# my_tic_tac_toe_board.net
KiCad netlist of a schematic drawn in EAGLE
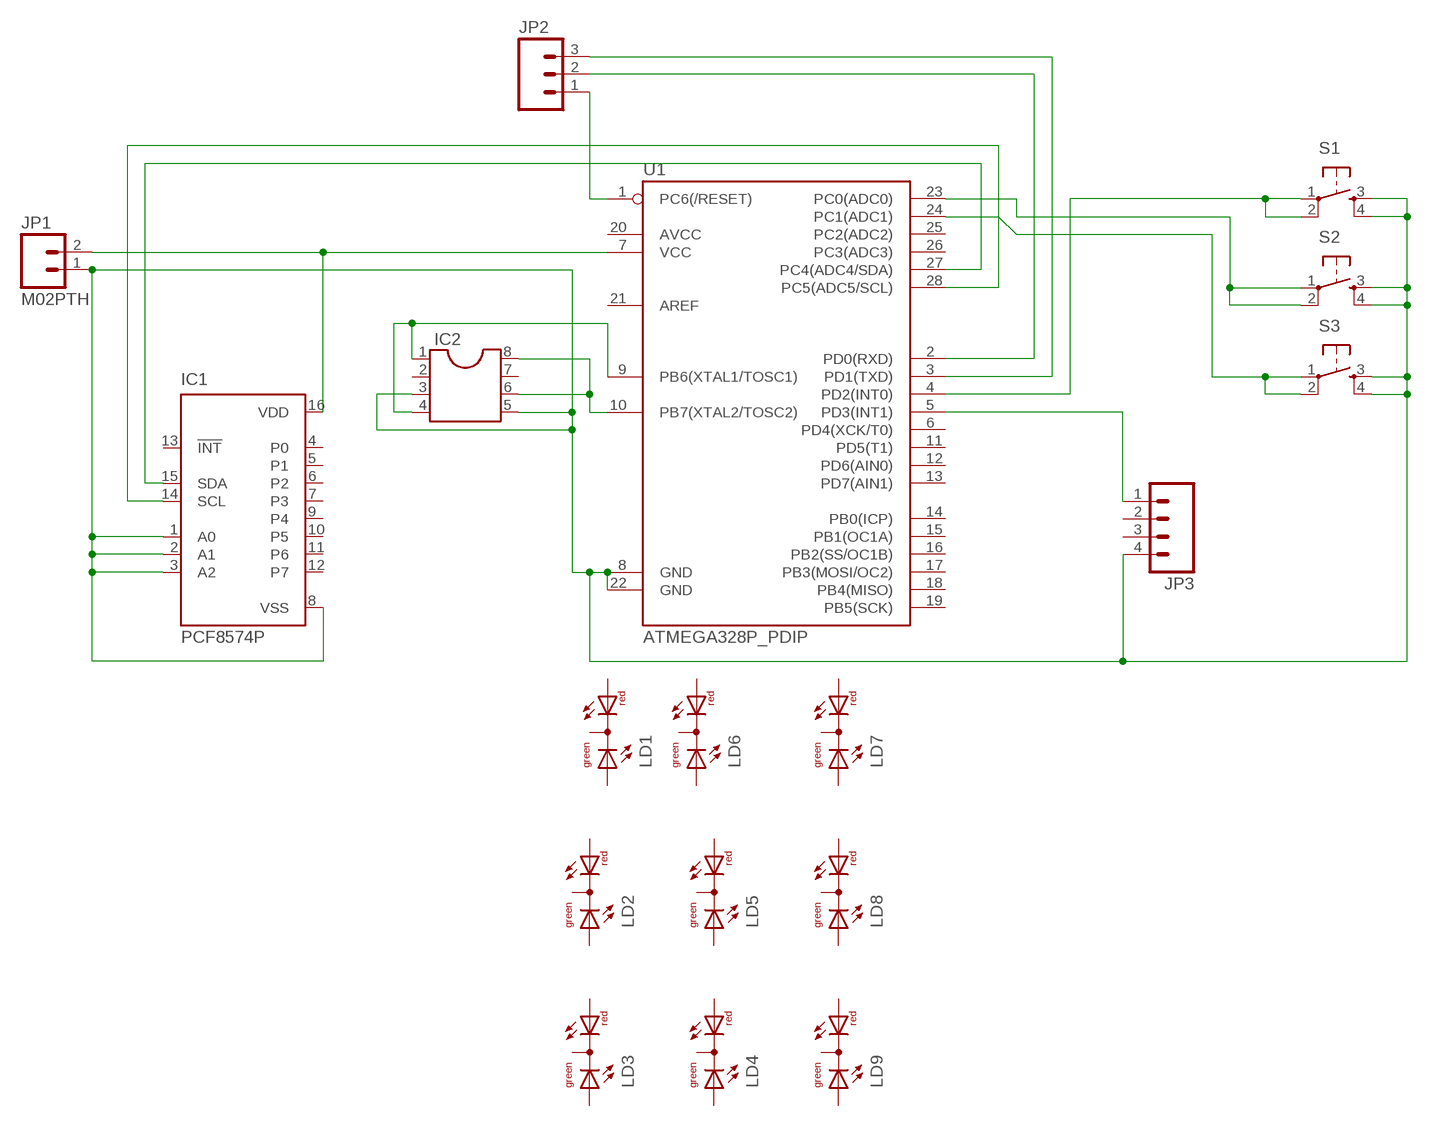
[diagram p0: schematic, sheet 1]

(export (version "E")
  (design (tool "Eeschema 10.0.6"))
  (components
    (comp (ref "IC1")
      (value "PCF8574P")
      (footprint "eagle-import:DIL16")
      (fields (field (name "MPN") "PCF8574PN"))
      (libsource (lib "eagle-import") (part "PCF8574P"))
    )
    (comp (ref "IC2")
      (value "DIL8S")
      (footprint "eagle-import:SOCKET-08")
      (libsource (lib "eagle-import") (part "DIL8S"))
    )
    (comp (ref "JP1")
      (value "M02PTH")
      (footprint "eagle-import:1X02")
      (libsource (lib "eagle-import") (part "M02PTH"))
    )
    (comp (ref "JP2")
      (value "M03PTH")
      (footprint "eagle-import:1X03")
      (libsource (lib "eagle-import") (part "M03PTH"))
    )
    (comp (ref "JP3")
      (value "M04PTH")
      (footprint "eagle-import:1X04")
      (libsource (lib "eagle-import") (part "M04PTH"))
    )
    (comp (ref "LD1")
      (value "DUOLED-RG-C")
      (footprint "eagle-import:DUOLED-C-5MM")
      (libsource (lib "eagle-import") (part "DUOLED-RG-C"))
    )
    (comp (ref "LD2")
      (value "DUOLED-RG-C")
      (footprint "eagle-import:DUOLED-C-5MM")
      (libsource (lib "eagle-import") (part "DUOLED-RG-C"))
    )
    (comp (ref "LD3")
      (value "DUOLED-RG-C")
      (footprint "eagle-import:DUOLED-C-5MM")
      (libsource (lib "eagle-import") (part "DUOLED-RG-C"))
    )
    (comp (ref "LD4")
      (value "DUOLED-RG-C")
      (footprint "eagle-import:DUOLED-C-5MM")
      (libsource (lib "eagle-import") (part "DUOLED-RG-C"))
    )
    (comp (ref "LD5")
      (value "DUOLED-RG-C")
      (footprint "eagle-import:DUOLED-C-5MM")
      (libsource (lib "eagle-import") (part "DUOLED-RG-C"))
    )
    (comp (ref "LD6")
      (value "DUOLED-RG-C")
      (footprint "eagle-import:DUOLED-C-5MM")
      (libsource (lib "eagle-import") (part "DUOLED-RG-C"))
    )
    (comp (ref "LD7")
      (value "DUOLED-RG-C")
      (footprint "eagle-import:DUOLED-C-5MM")
      (libsource (lib "eagle-import") (part "DUOLED-RG-C"))
    )
    (comp (ref "LD8")
      (value "DUOLED-RG-C")
      (footprint "eagle-import:DUOLED-C-5MM")
      (libsource (lib "eagle-import") (part "DUOLED-RG-C"))
    )
    (comp (ref "LD9")
      (value "DUOLED-RG-C")
      (footprint "eagle-import:DUOLED-C-5MM")
      (libsource (lib "eagle-import") (part "DUOLED-RG-C"))
    )
    (comp (ref "S1")
      (value "TAC_SWITCHPTH")
      (footprint "eagle-import:TACTILE-PTH")
      (libsource (lib "eagle-import") (part "TAC_SWITCHPTH"))
    )
    (comp (ref "S2")
      (value "TAC_SWITCHPTH")
      (footprint "eagle-import:TACTILE-PTH")
      (libsource (lib "eagle-import") (part "TAC_SWITCHPTH"))
    )
    (comp (ref "S3")
      (value "TAC_SWITCHPTH")
      (footprint "eagle-import:TACTILE-PTH")
      (libsource (lib "eagle-import") (part "TAC_SWITCHPTH"))
    )
    (comp (ref "U1")
      (value "ATMEGA328P_PDIP")
      (footprint "eagle-import:DIL28-3")
      (libsource (lib "eagle-import") (part "ATMEGA328P_PDIP"))
    )
  )
  (nets
    (net (code "1") (name "Net-(IC1-A0)") (class "Default")
      (node (ref "IC1") (pin "1") (pinfunction "A0_1") (pintype "input"))
      (node (ref "IC1") (pin "2") (pinfunction "A1_2") (pintype "input"))
      (node (ref "IC1") (pin "3") (pinfunction "A2_3") (pintype "input"))
      (node (ref "IC1") (pin "8") (pinfunction "VSS_8") (pintype "power_in"))
      (node (ref "IC2") (pin "3") (pinfunction "3_3") (pintype "passive"))
      (node (ref "IC2") (pin "5") (pinfunction "5_5") (pintype "passive"))
      (node (ref "JP1") (pin "1") (pinfunction "1_1") (pintype "passive"))
      (node (ref "JP3") (pin "4") (pinfunction "4_4") (pintype "passive"))
      (node (ref "S1") (pin "3") (pinfunction "3_3") (pintype "passive"))
      (node (ref "S1") (pin "4") (pinfunction "4_4") (pintype "passive"))
      (node (ref "S2") (pin "3") (pinfunction "3_3") (pintype "passive"))
      (node (ref "S2") (pin "4") (pinfunction "4_4") (pintype "passive"))
      (node (ref "S3") (pin "3") (pinfunction "3_3") (pintype "passive"))
      (node (ref "S3") (pin "4") (pinfunction "4_4") (pintype "passive"))
      (node (ref "U1") (pin "22") (pinfunction "GND_22") (pintype "bidirectional"))
      (node (ref "U1") (pin "8") (pinfunction "GND_8") (pintype "bidirectional"))
    )
    (net (code "2") (name "Net-(IC1-SCL)") (class "Default")
      (node (ref "IC1") (pin "14") (pinfunction "SCL_14") (pintype "input"))
      (node (ref "U1") (pin "28") (pinfunction "PC5(ADC5/SCL)_28") (pintype "bidirectional"))
    )
    (net (code "3") (name "Net-(IC1-SDA)") (class "Default")
      (node (ref "IC1") (pin "15") (pinfunction "SDA_15") (pintype "bidirectional"))
      (node (ref "U1") (pin "27") (pinfunction "PC4(ADC4/SDA)_27") (pintype "bidirectional"))
    )
    (net (code "4") (name "Net-(IC1-VDD)") (class "Default")
      (node (ref "IC1") (pin "16") (pinfunction "VDD_16") (pintype "power_in"))
      (node (ref "JP1") (pin "2") (pinfunction "2_2") (pintype "passive"))
      (node (ref "U1") (pin "7") (pinfunction "VCC_7") (pintype "bidirectional"))
    )
    (net (code "5") (name "Net-(U1-PB6(XTAL1{slash}TOSC1))") (class "Default")
      (node (ref "IC2") (pin "1") (pinfunction "1_1") (pintype "passive"))
      (node (ref "IC2") (pin "4") (pinfunction "4_4") (pintype "passive"))
      (node (ref "U1") (pin "9") (pinfunction "PB6(XTAL1/TOSC1)_9") (pintype "bidirectional"))
    )
    (net (code "6") (name "Net-(U1-PB7(XTAL2{slash}TOSC2))") (class "Default")
      (node (ref "IC2") (pin "6") (pinfunction "6_6") (pintype "passive"))
      (node (ref "IC2") (pin "8") (pinfunction "8_8") (pintype "passive"))
      (node (ref "U1") (pin "10") (pinfunction "PB7(XTAL2/TOSC2)_10") (pintype "bidirectional"))
    )
    (net (code "7") (name "Net-(U1-PC0(ADC0))") (class "Default")
      (node (ref "S2") (pin "1") (pinfunction "1_1") (pintype "passive"))
      (node (ref "S2") (pin "2") (pinfunction "2_2") (pintype "passive"))
      (node (ref "U1") (pin "23") (pinfunction "PC0(ADC0)_23") (pintype "bidirectional"))
    )
    (net (code "8") (name "Net-(U1-PC1(ADC1))") (class "Default")
      (node (ref "S3") (pin "1") (pinfunction "1_1") (pintype "passive"))
      (node (ref "S3") (pin "2") (pinfunction "2_2") (pintype "passive"))
      (node (ref "U1") (pin "24") (pinfunction "PC1(ADC1)_24") (pintype "bidirectional"))
    )
    (net (code "9") (name "Net-(U1-PC6({slash}RESET))") (class "Default")
      (node (ref "JP2") (pin "1") (pinfunction "1_1") (pintype "passive"))
      (node (ref "U1") (pin "1") (pinfunction "PC6(/RESET)_1") (pintype "bidirectional"))
    )
    (net (code "10") (name "Net-(U1-PD0(RXD))") (class "Default")
      (node (ref "JP2") (pin "2") (pinfunction "2_2") (pintype "passive"))
      (node (ref "U1") (pin "2") (pinfunction "PD0(RXD)_2") (pintype "bidirectional"))
    )
    (net (code "11") (name "Net-(U1-PD1(TXD))") (class "Default")
      (node (ref "JP2") (pin "3") (pinfunction "3_3") (pintype "passive"))
      (node (ref "U1") (pin "3") (pinfunction "PD1(TXD)_3") (pintype "bidirectional"))
    )
    (net (code "12") (name "Net-(U1-PD2(INT0))") (class "Default")
      (node (ref "S1") (pin "1") (pinfunction "1_1") (pintype "passive"))
      (node (ref "S1") (pin "2") (pinfunction "2_2") (pintype "passive"))
      (node (ref "U1") (pin "4") (pinfunction "PD2(INT0)_4") (pintype "bidirectional"))
    )
    (net (code "13") (name "Net-(U1-PD3(INT1))") (class "Default")
      (node (ref "JP3") (pin "1") (pinfunction "1_1") (pintype "passive"))
      (node (ref "U1") (pin "5") (pinfunction "PD3(INT1)_5") (pintype "bidirectional"))
    )
    (net (code "14") (name "unconnected-(IC1-P0-Pad4)") (class "Default")
      (node (ref "IC1") (pin "4") (pinfunction "P0_4") (pintype "bidirectional"))
    )
    (net (code "15") (name "unconnected-(IC1-P1-Pad5)") (class "Default")
      (node (ref "IC1") (pin "5") (pinfunction "P1_5") (pintype "bidirectional"))
    )
    (net (code "16") (name "unconnected-(IC1-P2-Pad6)") (class "Default")
      (node (ref "IC1") (pin "6") (pinfunction "P2_6") (pintype "bidirectional"))
    )
    (net (code "17") (name "unconnected-(IC1-P3-Pad7)") (class "Default")
      (node (ref "IC1") (pin "7") (pinfunction "P3_7") (pintype "bidirectional"))
    )
    (net (code "18") (name "unconnected-(IC1-P4-Pad9)") (class "Default")
      (node (ref "IC1") (pin "9") (pinfunction "P4_9") (pintype "bidirectional"))
    )
    (net (code "19") (name "unconnected-(IC1-P5-Pad10)") (class "Default")
      (node (ref "IC1") (pin "10") (pinfunction "P5_10") (pintype "bidirectional"))
    )
    (net (code "20") (name "unconnected-(IC1-P6-Pad11)") (class "Default")
      (node (ref "IC1") (pin "11") (pinfunction "P6_11") (pintype "bidirectional"))
    )
    (net (code "21") (name "unconnected-(IC1-P7-Pad12)") (class "Default")
      (node (ref "IC1") (pin "12") (pinfunction "P7_12") (pintype "bidirectional"))
    )
    (net (code "22") (name "unconnected-(IC1-~{INT}-Pad13)") (class "Default")
      (node (ref "IC1") (pin "13") (pinfunction "~{INT}_13") (pintype "output"))
    )
    (net (code "23") (name "unconnected-(IC2-Pad2)") (class "Default")
      (node (ref "IC2") (pin "2") (pinfunction "2_2") (pintype "passive"))
    )
    (net (code "24") (name "unconnected-(IC2-Pad7)") (class "Default")
      (node (ref "IC2") (pin "7") (pinfunction "7_7") (pintype "passive"))
    )
    (net (code "25") (name "unconnected-(JP3-Pad2)") (class "Default")
      (node (ref "JP3") (pin "2") (pinfunction "2_2") (pintype "passive"))
    )
    (net (code "26") (name "unconnected-(JP3-Pad3)") (class "Default")
      (node (ref "JP3") (pin "3") (pinfunction "3_3") (pintype "passive"))
    )
    (net (code "27") (name "unconnected-(LD1-AG-PadAX)") (class "Default")
      (node (ref "LD1") (pin "AX") (pinfunction "AG_AX") (pintype "passive"))
    )
    (net (code "28") (name "unconnected-(LD1-PadAR)") (class "Default")
      (node (ref "LD1") (pin "AR") (pinfunction "AR_AR") (pintype "passive"))
    )
    (net (code "29") (name "unconnected-(LD1-PadC)") (class "Default")
      (node (ref "LD1") (pin "C") (pinfunction "C_C") (pintype "passive"))
    )
    (net (code "30") (name "unconnected-(LD2-AG-PadAX)") (class "Default")
      (node (ref "LD2") (pin "AX") (pinfunction "AG_AX") (pintype "passive"))
    )
    (net (code "31") (name "unconnected-(LD2-PadAR)") (class "Default")
      (node (ref "LD2") (pin "AR") (pinfunction "AR_AR") (pintype "passive"))
    )
    (net (code "32") (name "unconnected-(LD2-PadC)") (class "Default")
      (node (ref "LD2") (pin "C") (pinfunction "C_C") (pintype "passive"))
    )
    (net (code "33") (name "unconnected-(LD3-AG-PadAX)") (class "Default")
      (node (ref "LD3") (pin "AX") (pinfunction "AG_AX") (pintype "passive"))
    )
    (net (code "34") (name "unconnected-(LD3-PadAR)") (class "Default")
      (node (ref "LD3") (pin "AR") (pinfunction "AR_AR") (pintype "passive"))
    )
    (net (code "35") (name "unconnected-(LD3-PadC)") (class "Default")
      (node (ref "LD3") (pin "C") (pinfunction "C_C") (pintype "passive"))
    )
    (net (code "36") (name "unconnected-(LD4-AG-PadAX)") (class "Default")
      (node (ref "LD4") (pin "AX") (pinfunction "AG_AX") (pintype "passive"))
    )
    (net (code "37") (name "unconnected-(LD4-PadAR)") (class "Default")
      (node (ref "LD4") (pin "AR") (pinfunction "AR_AR") (pintype "passive"))
    )
    (net (code "38") (name "unconnected-(LD4-PadC)") (class "Default")
      (node (ref "LD4") (pin "C") (pinfunction "C_C") (pintype "passive"))
    )
    (net (code "39") (name "unconnected-(LD5-AG-PadAX)") (class "Default")
      (node (ref "LD5") (pin "AX") (pinfunction "AG_AX") (pintype "passive"))
    )
    (net (code "40") (name "unconnected-(LD5-PadAR)") (class "Default")
      (node (ref "LD5") (pin "AR") (pinfunction "AR_AR") (pintype "passive"))
    )
    (net (code "41") (name "unconnected-(LD5-PadC)") (class "Default")
      (node (ref "LD5") (pin "C") (pinfunction "C_C") (pintype "passive"))
    )
    (net (code "42") (name "unconnected-(LD6-AG-PadAX)") (class "Default")
      (node (ref "LD6") (pin "AX") (pinfunction "AG_AX") (pintype "passive"))
    )
    (net (code "43") (name "unconnected-(LD6-PadAR)") (class "Default")
      (node (ref "LD6") (pin "AR") (pinfunction "AR_AR") (pintype "passive"))
    )
    (net (code "44") (name "unconnected-(LD6-PadC)") (class "Default")
      (node (ref "LD6") (pin "C") (pinfunction "C_C") (pintype "passive"))
    )
    (net (code "45") (name "unconnected-(LD7-AG-PadAX)") (class "Default")
      (node (ref "LD7") (pin "AX") (pinfunction "AG_AX") (pintype "passive"))
    )
    (net (code "46") (name "unconnected-(LD7-PadAR)") (class "Default")
      (node (ref "LD7") (pin "AR") (pinfunction "AR_AR") (pintype "passive"))
    )
    (net (code "47") (name "unconnected-(LD7-PadC)") (class "Default")
      (node (ref "LD7") (pin "C") (pinfunction "C_C") (pintype "passive"))
    )
    (net (code "48") (name "unconnected-(LD8-AG-PadAX)") (class "Default")
      (node (ref "LD8") (pin "AX") (pinfunction "AG_AX") (pintype "passive"))
    )
    (net (code "49") (name "unconnected-(LD8-PadAR)") (class "Default")
      (node (ref "LD8") (pin "AR") (pinfunction "AR_AR") (pintype "passive"))
    )
    (net (code "50") (name "unconnected-(LD8-PadC)") (class "Default")
      (node (ref "LD8") (pin "C") (pinfunction "C_C") (pintype "passive"))
    )
    (net (code "51") (name "unconnected-(LD9-AG-PadAX)") (class "Default")
      (node (ref "LD9") (pin "AX") (pinfunction "AG_AX") (pintype "passive"))
    )
    (net (code "52") (name "unconnected-(LD9-PadAR)") (class "Default")
      (node (ref "LD9") (pin "AR") (pinfunction "AR_AR") (pintype "passive"))
    )
    (net (code "53") (name "unconnected-(LD9-PadC)") (class "Default")
      (node (ref "LD9") (pin "C") (pinfunction "C_C") (pintype "passive"))
    )
    (net (code "54") (name "unconnected-(U1-AREF-Pad21)") (class "Default")
      (node (ref "U1") (pin "21") (pinfunction "AREF_21") (pintype "bidirectional"))
    )
    (net (code "55") (name "unconnected-(U1-AVCC-Pad20)") (class "Default")
      (node (ref "U1") (pin "20") (pinfunction "AVCC_20") (pintype "bidirectional"))
    )
    (net (code "56") (name "unconnected-(U1-PB0(ICP)-Pad14)") (class "Default")
      (node (ref "U1") (pin "14") (pinfunction "PB0(ICP)_14") (pintype "bidirectional"))
    )
    (net (code "57") (name "unconnected-(U1-PB1(OC1A)-Pad15)") (class "Default")
      (node (ref "U1") (pin "15") (pinfunction "PB1(OC1A)_15") (pintype "bidirectional"))
    )
    (net (code "58") (name "unconnected-(U1-PB2(SS{slash}OC1B)-Pad16)") (class "Default")
      (node (ref "U1") (pin "16") (pinfunction "PB2(SS/OC1B)_16") (pintype "bidirectional"))
    )
    (net (code "59") (name "unconnected-(U1-PB3(MOSI{slash}OC2)-Pad17)") (class "Default")
      (node (ref "U1") (pin "17") (pinfunction "PB3(MOSI/OC2)_17") (pintype "bidirectional"))
    )
    (net (code "60") (name "unconnected-(U1-PB4(MISO)-Pad18)") (class "Default")
      (node (ref "U1") (pin "18") (pinfunction "PB4(MISO)_18") (pintype "bidirectional"))
    )
    (net (code "61") (name "unconnected-(U1-PB5(SCK)-Pad19)") (class "Default")
      (node (ref "U1") (pin "19") (pinfunction "PB5(SCK)_19") (pintype "bidirectional"))
    )
    (net (code "62") (name "unconnected-(U1-PC2(ADC2)-Pad25)") (class "Default")
      (node (ref "U1") (pin "25") (pinfunction "PC2(ADC2)_25") (pintype "bidirectional"))
    )
    (net (code "63") (name "unconnected-(U1-PC3(ADC3)-Pad26)") (class "Default")
      (node (ref "U1") (pin "26") (pinfunction "PC3(ADC3)_26") (pintype "bidirectional"))
    )
    (net (code "64") (name "unconnected-(U1-PD4(XCK{slash}T0)-Pad6)") (class "Default")
      (node (ref "U1") (pin "6") (pinfunction "PD4(XCK/T0)_6") (pintype "bidirectional"))
    )
    (net (code "65") (name "unconnected-(U1-PD5(T1)-Pad11)") (class "Default")
      (node (ref "U1") (pin "11") (pinfunction "PD5(T1)_11") (pintype "bidirectional"))
    )
    (net (code "66") (name "unconnected-(U1-PD6(AIN0)-Pad12)") (class "Default")
      (node (ref "U1") (pin "12") (pinfunction "PD6(AIN0)_12") (pintype "bidirectional"))
    )
    (net (code "67") (name "unconnected-(U1-PD7(AIN1)-Pad13)") (class "Default")
      (node (ref "U1") (pin "13") (pinfunction "PD7(AIN1)_13") (pintype "bidirectional"))
    )
  )
)
